# GearIndicator_disp.net
KiCad netlist of a schematic drawn in EAGLE
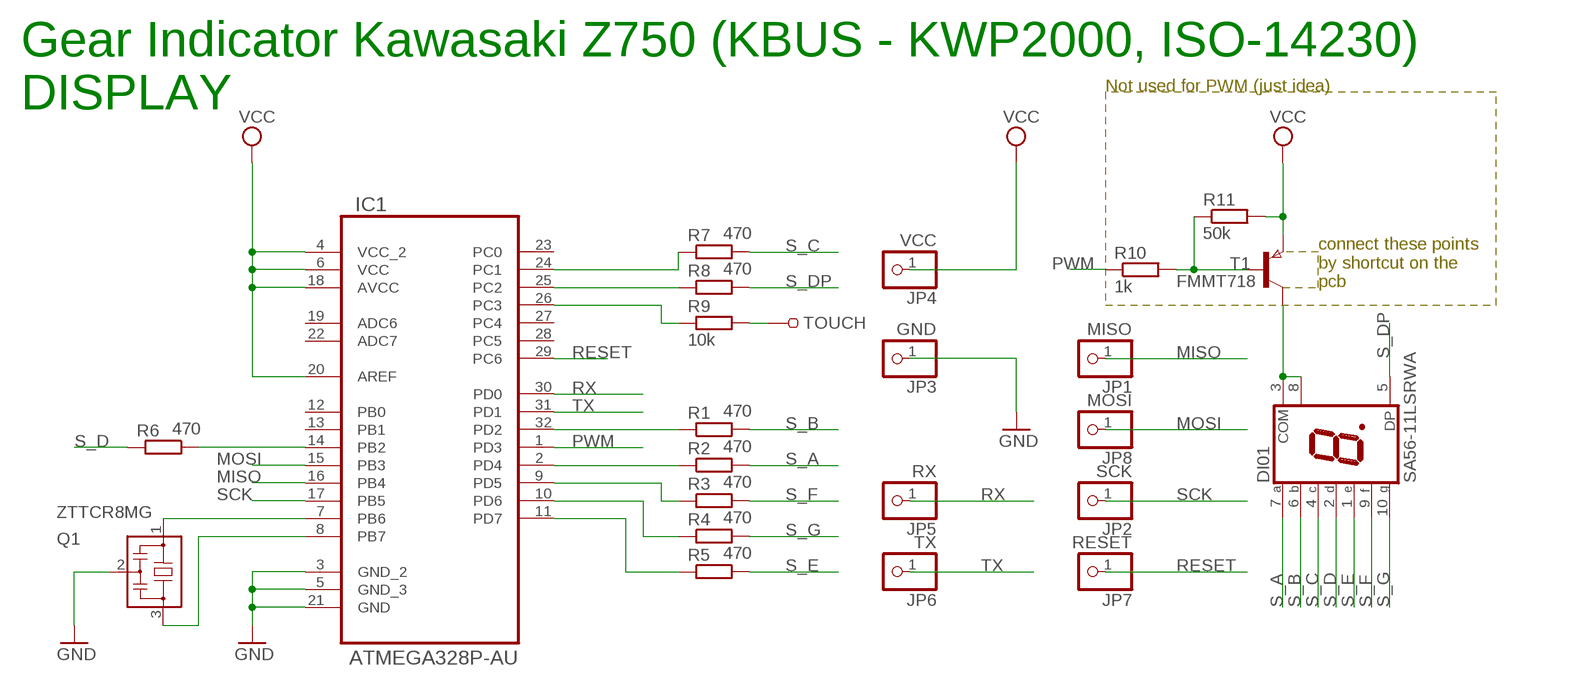
[diagram p0: schematic, sheet 1]

(export (version "E")
  (design (tool "Eeschema 10.0.6"))
  (components
    (comp (ref "DI01")
      (value "SA56-11LSRWA")
      (footprint "eagle-import:SA56-11")
      (libsource (lib "eagle-import") (part "7-SEG_SA56-11"))
    )
    (comp (ref "IC1")
      (value "ATMEGA328P-AU")
      (footprint "eagle-import:QFP80P900X900X120-32N")
      (libsource (lib "eagle-import") (part "ATMEGA328P-AU"))
    )
    (comp (ref "JP1")
      (value "MISO")
      (footprint "eagle-import:PIN1")
      (libsource (lib "eagle-import") (part "PIN1"))
    )
    (comp (ref "JP2")
      (value "SCK")
      (footprint "eagle-import:PIN1")
      (libsource (lib "eagle-import") (part "PIN1"))
    )
    (comp (ref "JP3")
      (value "GND")
      (footprint "eagle-import:PIN1")
      (libsource (lib "eagle-import") (part "PIN1"))
    )
    (comp (ref "JP4")
      (value "VCC")
      (footprint "eagle-import:PIN1")
      (libsource (lib "eagle-import") (part "PIN1"))
    )
    (comp (ref "JP5")
      (value "RX")
      (footprint "eagle-import:PIN1")
      (libsource (lib "eagle-import") (part "PIN1"))
    )
    (comp (ref "JP6")
      (value "TX")
      (footprint "eagle-import:PIN1")
      (libsource (lib "eagle-import") (part "PIN1"))
    )
    (comp (ref "JP7")
      (value "RESET")
      (footprint "eagle-import:PIN1")
      (libsource (lib "eagle-import") (part "PIN1"))
    )
    (comp (ref "JP8")
      (value "MOSI")
      (footprint "eagle-import:PIN1")
      (libsource (lib "eagle-import") (part "PIN1"))
    )
    (comp (ref "Q1")
      (value "ZTTCR8MG")
      (footprint "eagle-import:ZTTCR")
      (libsource (lib "eagle-import") (part "ZTTCR"))
    )
    (comp (ref "R1")
      (value "470")
      (footprint "eagle-import:R0603")
      (libsource (lib "eagle-import") (part "R-EU_R0603"))
    )
    (comp (ref "R2")
      (value "470")
      (footprint "eagle-import:R0603")
      (libsource (lib "eagle-import") (part "R-EU_R0603"))
    )
    (comp (ref "R3")
      (value "470")
      (footprint "eagle-import:R0603")
      (libsource (lib "eagle-import") (part "R-EU_R0603"))
    )
    (comp (ref "R4")
      (value "470")
      (footprint "eagle-import:R0603")
      (libsource (lib "eagle-import") (part "R-EU_R0603"))
    )
    (comp (ref "R5")
      (value "470")
      (footprint "eagle-import:R0603")
      (libsource (lib "eagle-import") (part "R-EU_R0603"))
    )
    (comp (ref "R6")
      (value "470")
      (footprint "eagle-import:R0603")
      (libsource (lib "eagle-import") (part "R-EU_R0603"))
    )
    (comp (ref "R7")
      (value "470")
      (footprint "eagle-import:R0603")
      (libsource (lib "eagle-import") (part "R-EU_R0603"))
    )
    (comp (ref "R8")
      (value "470")
      (footprint "eagle-import:R0603")
      (libsource (lib "eagle-import") (part "R-EU_R0603"))
    )
    (comp (ref "R9")
      (value "10k")
      (footprint "eagle-import:R0603")
      (libsource (lib "eagle-import") (part "R-EU_R0603"))
    )
    (comp (ref "R10")
      (value "1k")
      (footprint "eagle-import:R0603")
      (libsource (lib "eagle-import") (part "R-EU_R0603"))
    )
    (comp (ref "R11")
      (value "50k")
      (footprint "eagle-import:R0603")
      (libsource (lib "eagle-import") (part "R-EU_R0603"))
    )
    (comp (ref "T1")
      (value "FMMT718")
      (footprint "eagle-import:SOT-23")
      (libsource (lib "eagle-import") (part "FMMT718"))
    )
    (comp (ref "TOUCH")
      (value "SMD1")
      (footprint "eagle-import:SMD_2X2")
      (libsource (lib "eagle-import") (part "SMD1"))
    )
  )
  (nets
    (net (code "1") (name "/MISO") (class "Default")
      (node (ref "IC1") (pin "16") (pinfunction "PB4_16") (pintype "bidirectional"))
      (node (ref "JP1") (pin "1") (pinfunction "1_1") (pintype "passive"))
    )
    (net (code "2") (name "/MOSI") (class "Default")
      (node (ref "IC1") (pin "15") (pinfunction "PB3_15") (pintype "bidirectional"))
      (node (ref "JP8") (pin "1") (pinfunction "1_1") (pintype "passive"))
    )
    (net (code "3") (name "/PWM") (class "Default")
      (node (ref "IC1") (pin "1") (pinfunction "PD3_1") (pintype "bidirectional"))
      (node (ref "R10") (pin "1") (pinfunction "1_1") (pintype "passive"))
    )
    (net (code "4") (name "/RESET") (class "Default")
      (node (ref "IC1") (pin "29") (pinfunction "PC6_29") (pintype "bidirectional"))
      (node (ref "JP7") (pin "1") (pinfunction "1_1") (pintype "passive"))
    )
    (net (code "5") (name "/RX") (class "Default")
      (node (ref "IC1") (pin "30") (pinfunction "PD0_30") (pintype "bidirectional"))
      (node (ref "JP5") (pin "1") (pinfunction "1_1") (pintype "passive"))
    )
    (net (code "6") (name "/SCK") (class "Default")
      (node (ref "IC1") (pin "17") (pinfunction "PB5_17") (pintype "bidirectional"))
      (node (ref "JP2") (pin "1") (pinfunction "1_1") (pintype "passive"))
    )
    (net (code "7") (name "/S_A") (class "Default")
      (node (ref "DI01") (pin "7") (pinfunction "A_7") (pintype "passive"))
      (node (ref "R2") (pin "2") (pinfunction "2_2") (pintype "passive"))
    )
    (net (code "8") (name "/S_B") (class "Default")
      (node (ref "DI01") (pin "6") (pinfunction "B_6") (pintype "passive"))
      (node (ref "R1") (pin "2") (pinfunction "2_2") (pintype "passive"))
    )
    (net (code "9") (name "/S_C") (class "Default")
      (node (ref "DI01") (pin "4") (pinfunction "C_4") (pintype "passive"))
      (node (ref "R7") (pin "2") (pinfunction "2_2") (pintype "passive"))
    )
    (net (code "10") (name "/S_D") (class "Default")
      (node (ref "DI01") (pin "2") (pinfunction "D_2") (pintype "passive"))
      (node (ref "R6") (pin "2") (pinfunction "2_2") (pintype "passive"))
    )
    (net (code "11") (name "/S_DP") (class "Default")
      (node (ref "DI01") (pin "5") (pinfunction "DP_5") (pintype "passive"))
      (node (ref "R8") (pin "2") (pinfunction "2_2") (pintype "passive"))
    )
    (net (code "12") (name "/S_E") (class "Default")
      (node (ref "DI01") (pin "1") (pinfunction "E_1") (pintype "passive"))
      (node (ref "R5") (pin "2") (pinfunction "2_2") (pintype "passive"))
    )
    (net (code "13") (name "/S_F") (class "Default")
      (node (ref "DI01") (pin "9") (pinfunction "F_9") (pintype "passive"))
      (node (ref "R3") (pin "2") (pinfunction "2_2") (pintype "passive"))
    )
    (net (code "14") (name "/S_G") (class "Default")
      (node (ref "DI01") (pin "10") (pinfunction "G_10") (pintype "passive"))
      (node (ref "R4") (pin "2") (pinfunction "2_2") (pintype "passive"))
    )
    (net (code "15") (name "/TX") (class "Default")
      (node (ref "IC1") (pin "31") (pinfunction "PD1_31") (pintype "bidirectional"))
      (node (ref "JP6") (pin "1") (pinfunction "1_1") (pintype "passive"))
    )
    (net (code "16") (name "GND") (class "Default")
      (node (ref "IC1") (pin "21") (pinfunction "GND_21") (pintype "passive"))
      (node (ref "IC1") (pin "3") (pinfunction "GND_2_3") (pintype "passive"))
      (node (ref "IC1") (pin "5") (pinfunction "GND_3_5") (pintype "passive"))
      (node (ref "JP3") (pin "1") (pinfunction "1_1") (pintype "passive"))
      (node (ref "Q1") (pin "2") (pinfunction "2_2") (pintype "passive"))
    )
    (net (code "17") (name "Net-(IC1-PB2)") (class "Default")
      (node (ref "IC1") (pin "14") (pinfunction "PB2_14") (pintype "bidirectional"))
      (node (ref "R6") (pin "1") (pinfunction "1_1") (pintype "passive"))
    )
    (net (code "18") (name "Net-(IC1-PB6)") (class "Default")
      (node (ref "IC1") (pin "7") (pinfunction "PB6_7") (pintype "bidirectional"))
      (node (ref "Q1") (pin "1") (pinfunction "1_1") (pintype "passive"))
    )
    (net (code "19") (name "Net-(IC1-PB7)") (class "Default")
      (node (ref "IC1") (pin "8") (pinfunction "PB7_8") (pintype "bidirectional"))
      (node (ref "Q1") (pin "3") (pinfunction "3_3") (pintype "passive"))
    )
    (net (code "20") (name "Net-(IC1-PC1)") (class "Default")
      (node (ref "IC1") (pin "24") (pinfunction "PC1_24") (pintype "bidirectional"))
      (node (ref "R7") (pin "1") (pinfunction "1_1") (pintype "passive"))
    )
    (net (code "21") (name "Net-(IC1-PC2)") (class "Default")
      (node (ref "IC1") (pin "25") (pinfunction "PC2_25") (pintype "bidirectional"))
      (node (ref "R8") (pin "1") (pinfunction "1_1") (pintype "passive"))
    )
    (net (code "22") (name "Net-(IC1-PC3)") (class "Default")
      (node (ref "IC1") (pin "26") (pinfunction "PC3_26") (pintype "bidirectional"))
      (node (ref "R9") (pin "1") (pinfunction "1_1") (pintype "passive"))
    )
    (net (code "23") (name "Net-(IC1-PD2)") (class "Default")
      (node (ref "IC1") (pin "32") (pinfunction "PD2_32") (pintype "bidirectional"))
      (node (ref "R1") (pin "1") (pinfunction "1_1") (pintype "passive"))
    )
    (net (code "24") (name "Net-(IC1-PD4)") (class "Default")
      (node (ref "IC1") (pin "2") (pinfunction "PD4_2") (pintype "bidirectional"))
      (node (ref "R2") (pin "1") (pinfunction "1_1") (pintype "passive"))
    )
    (net (code "25") (name "Net-(IC1-PD5)") (class "Default")
      (node (ref "IC1") (pin "9") (pinfunction "PD5_9") (pintype "bidirectional"))
      (node (ref "R3") (pin "1") (pinfunction "1_1") (pintype "passive"))
    )
    (net (code "26") (name "Net-(IC1-PD6)") (class "Default")
      (node (ref "IC1") (pin "10") (pinfunction "PD6_10") (pintype "bidirectional"))
      (node (ref "R4") (pin "1") (pinfunction "1_1") (pintype "passive"))
    )
    (net (code "27") (name "Net-(IC1-PD7)") (class "Default")
      (node (ref "IC1") (pin "11") (pinfunction "PD7_11") (pintype "bidirectional"))
      (node (ref "R5") (pin "1") (pinfunction "1_1") (pintype "passive"))
    )
    (net (code "28") (name "Net-(T1-B)") (class "Default")
      (node (ref "R10") (pin "2") (pinfunction "2_2") (pintype "passive"))
      (node (ref "R11") (pin "1") (pinfunction "1_1") (pintype "passive"))
      (node (ref "T1") (pin "3") (pinfunction "B_3") (pintype "passive"))
    )
    (net (code "29") (name "Net-(T1-C)") (class "Default")
      (node (ref "DI01") (pin "3") (pinfunction "COM_3") (pintype "passive"))
      (node (ref "DI01") (pin "8") (pinfunction "COM_8") (pintype "passive"))
      (node (ref "T1") (pin "1") (pinfunction "C_1") (pintype "passive"))
    )
    (net (code "30") (name "Net-(TOUCH-1)") (class "Default")
      (node (ref "R9") (pin "2") (pinfunction "2_2") (pintype "passive"))
      (node (ref "TOUCH") (pin "P$1") (pinfunction "1_P$1") (pintype "passive"))
    )
    (net (code "31") (name "VCC") (class "Default")
      (node (ref "IC1") (pin "18") (pinfunction "AVCC_18") (pintype "power_in"))
      (node (ref "IC1") (pin "20") (pinfunction "AREF_20") (pintype "input"))
      (node (ref "IC1") (pin "4") (pinfunction "VCC_2_4") (pintype "power_in"))
      (node (ref "IC1") (pin "6") (pinfunction "VCC_6") (pintype "power_in"))
      (node (ref "JP4") (pin "1") (pinfunction "1_1") (pintype "passive"))
      (node (ref "R11") (pin "2") (pinfunction "2_2") (pintype "passive"))
      (node (ref "T1") (pin "2") (pinfunction "E_2") (pintype "passive"))
    )
    (net (code "32") (name "unconnected-(IC1-ADC6-Pad19)") (class "Default")
      (node (ref "IC1") (pin "19") (pinfunction "ADC6_19") (pintype "input"))
    )
    (net (code "33") (name "unconnected-(IC1-ADC7-Pad22)") (class "Default")
      (node (ref "IC1") (pin "22") (pinfunction "ADC7_22") (pintype "input"))
    )
    (net (code "34") (name "unconnected-(IC1-PB0-Pad12)") (class "Default")
      (node (ref "IC1") (pin "12") (pinfunction "PB0_12") (pintype "bidirectional"))
    )
    (net (code "35") (name "unconnected-(IC1-PB1-Pad13)") (class "Default")
      (node (ref "IC1") (pin "13") (pinfunction "PB1_13") (pintype "bidirectional"))
    )
    (net (code "36") (name "unconnected-(IC1-PC0-Pad23)") (class "Default")
      (node (ref "IC1") (pin "23") (pinfunction "PC0_23") (pintype "bidirectional"))
    )
    (net (code "37") (name "unconnected-(IC1-PC4-Pad27)") (class "Default")
      (node (ref "IC1") (pin "27") (pinfunction "PC4_27") (pintype "bidirectional"))
    )
    (net (code "38") (name "unconnected-(IC1-PC5-Pad28)") (class "Default")
      (node (ref "IC1") (pin "28") (pinfunction "PC5_28") (pintype "bidirectional"))
    )
  )
)
